# time.net
KiCad netlist of a schematic drawn in EAGLE
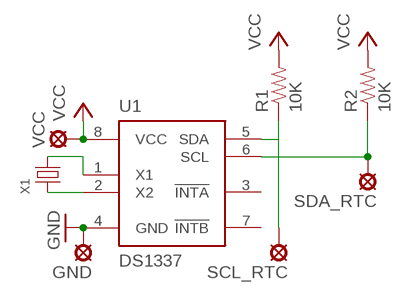
[diagram p0: schematic, sheet 1]

(export (version "E")
  (design (tool "Eeschema 10.0.6"))
  (components
    (comp (ref "GND")
      (value "SE13")
      (footprint "eagle-import:SE13")
      (libsource (lib "eagle-import") (part "SE13"))
    )
    (comp (ref "R1")
      (value "10K")
      (footprint "eagle-import:0603-RES")
      (libsource (lib "eagle-import") (part "10KOHM-1/10W-1%(0603)0603"))
    )
    (comp (ref "R2")
      (value "10K")
      (footprint "eagle-import:0603-RES")
      (libsource (lib "eagle-import") (part "10KOHM-1/10W-1%(0603)0603"))
    )
    (comp (ref "SCL_RTC")
      (value "SE13")
      (footprint "eagle-import:SE13")
      (libsource (lib "eagle-import") (part "SE13"))
    )
    (comp (ref "SDA_RTC")
      (value "SE13")
      (footprint "eagle-import:SE13")
      (libsource (lib "eagle-import") (part "SE13"))
    )
    (comp (ref "U1")
      (value "DS1337")
      (footprint "eagle-import:UMAX8")
      (libsource (lib "eagle-import") (part "DS1337"))
    )
    (comp (ref "VCC")
      (value "SE13")
      (footprint "eagle-import:SE13")
      (libsource (lib "eagle-import") (part "SE13"))
    )
    (comp (ref "X1")
      (value "CRYSTAL8X3.5MM")
      (footprint "eagle-import:CRYSTAL-8X3.5MM")
      (libsource (lib "eagle-import") (part "CRYSTAL8X3.5MM"))
    )
  )
  (nets
    (net (code "1") (name "GND") (class "Default")
      (node (ref "GND") (pin "MP") (pinfunction "MP_MP") (pintype "passive"))
      (node (ref "U1") (pin "4") (pinfunction "GND_4") (pintype "bidirectional"))
    )
    (net (code "2") (name "Net-(U1-SCL)") (class "Default")
      (node (ref "R2") (pin "1") (pinfunction "1_1") (pintype "passive"))
      (node (ref "SDA_RTC") (pin "MP") (pinfunction "MP_MP") (pintype "passive"))
      (node (ref "U1") (pin "6") (pinfunction "SCL_6") (pintype "bidirectional"))
    )
    (net (code "3") (name "Net-(U1-SDA)") (class "Default")
      (node (ref "R1") (pin "1") (pinfunction "1_1") (pintype "passive"))
      (node (ref "SCL_RTC") (pin "MP") (pinfunction "MP_MP") (pintype "passive"))
      (node (ref "U1") (pin "5") (pinfunction "SDA_5") (pintype "bidirectional"))
    )
    (net (code "4") (name "Net-(U1-X1)") (class "Default")
      (node (ref "U1") (pin "1") (pinfunction "X1_1") (pintype "bidirectional"))
      (node (ref "X1") (pin "4") (pinfunction "3_4") (pintype "bidirectional"))
    )
    (net (code "5") (name "Net-(U1-X2)") (class "Default")
      (node (ref "U1") (pin "2") (pinfunction "X2_2") (pintype "bidirectional"))
      (node (ref "X1") (pin "1") (pinfunction "1_1") (pintype "bidirectional"))
    )
    (net (code "6") (name "VCC") (class "Default")
      (node (ref "R1") (pin "2") (pinfunction "2_2") (pintype "passive"))
      (node (ref "R2") (pin "2") (pinfunction "2_2") (pintype "passive"))
      (node (ref "U1") (pin "8") (pinfunction "VCC_8") (pintype "bidirectional"))
      (node (ref "VCC") (pin "MP") (pinfunction "MP_MP") (pintype "passive"))
    )
    (net (code "7") (name "unconnected-(U1-~{INTA}-Pad3)") (class "Default")
      (node (ref "U1") (pin "3") (pinfunction "~{INTA}_3") (pintype "bidirectional"))
    )
    (net (code "8") (name "unconnected-(U1-~{INTB}-Pad7)") (class "Default")
      (node (ref "U1") (pin "7") (pinfunction "~{INTB}_7") (pintype "bidirectional"))
    )
  )
)
